# PSU_MAX1831_3V3_ALT.net
KiCad netlist of a schematic drawn in Altium Designer
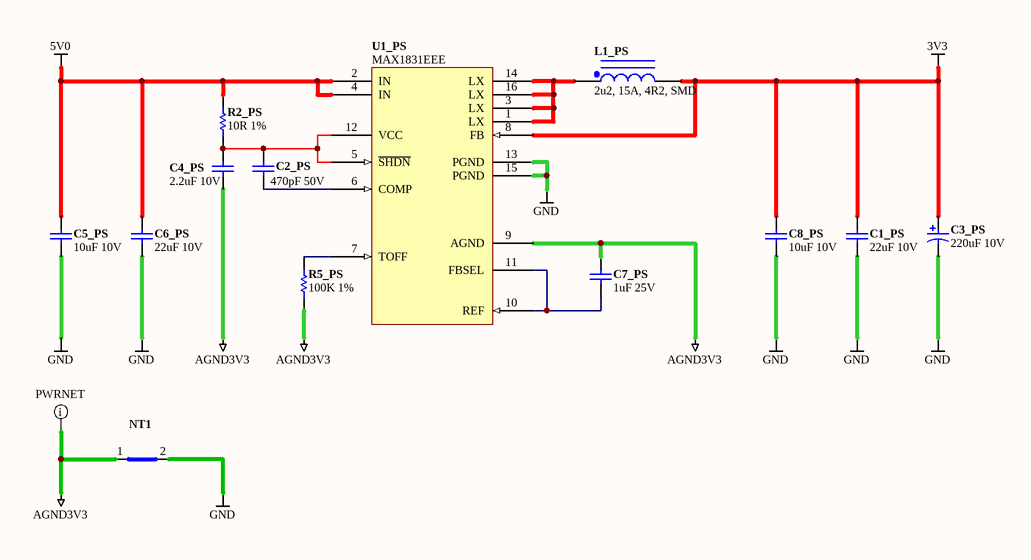
[diagram p0: PSU_MAX1831_3V3_ALT.SchDoc]

(export (version "E")
  (design (tool "Eeschema 10.0.6"))
  (components
    (comp (ref "C1_PS")
      (value "22uF 10V")
      (footprint "CAPC3225-STAR")
      (description "Capacitor, Ceramic, 22uF -20%/+80% 10V 1210 (3225) Y5V")
      (fields (field (name "TOLERANCE") "-20 / +80 %"))
      (libsource (lib "AltiumDesignLibrary") (part "CAP-NP"))
    )
    (comp (ref "C2_PS")
      (value "470pF 50V")
      (footprint "CAPC1005-STAR")
      (description "Capacitor, Ceramic, 470pF 5% 50V 0402 (1005) COG")
      (fields (field (name "TOLERANCE") "5 %"))
      (libsource (lib "AltiumDesignLibrary") (part "CAP-NP"))
    )
    (comp (ref "C3_PS")
      (value "220uF 10V")
      (footprint "CAPC7343-STAR")
      (description "Capacitor, Tantalum, 220uF 10% 10V MCCT-D (7343-31)")
      (fields (field (name "TOLERANCE") "10 %"))
      (libsource (lib "AltiumDesignLibrary") (part "CAP-P"))
    )
    (comp (ref "C4_PS")
      (value "2.2uF 10V")
      (footprint "CAPC1608-STAR")
      (description "Capacitor, Ceramic, 2.2uF 10% 10V 0603 (1608) X5R")
      (fields (field (name "TOLERANCE") "10 %"))
      (libsource (lib "AltiumDesignLibrary") (part "CAP-NP"))
    )
    (comp (ref "C5_PS")
      (value "10uF 10V")
      (footprint "CAPC2012-STAR")
      (description "Capacitor, Ceramic, 10uF 10% 10V 0805 (2012) X5R")
      (fields (field (name "TOLERANCE") "10 %"))
      (libsource (lib "AltiumDesignLibrary") (part "CAP-NP"))
    )
    (comp (ref "C6_PS")
      (value "22uF 10V")
      (footprint "CAPC3225-STAR")
      (description "Capacitor, Ceramic, 22uF -20%/+80% 10V 1210 (3225) Y5V")
      (fields (field (name "TOLERANCE") "-20 / +80 %"))
      (libsource (lib "AltiumDesignLibrary") (part "CAP-NP"))
    )
    (comp (ref "C7_PS")
      (value "1uF 25V")
      (footprint "CAPC3216-STAR")
      (description "Capacitor, Ceramic, 1uF 10% 25V 1206 (3216) X7R")
      (fields (field (name "TOLERANCE") "10 %"))
      (libsource (lib "AltiumDesignLibrary") (part "CAP-NP"))
    )
    (comp (ref "C8_PS")
      (value "10uF 10V")
      (footprint "CAPC2012-STAR")
      (description "Capacitor, Ceramic, 10uF 10% 10V 0805 (2012) X5R")
      (fields (field (name "TOLERANCE") "10 %"))
      (libsource (lib "AltiumDesignLibrary") (part "CAP-NP"))
    )
    (comp (ref "L1_PS")
      (value "2u2, 15A, 4R2, SMD")
      (footprint "IND-EPCOS-SMD-B82559")
      (description "Inductor, 2.2uH, 15A, 4R2, SMD")
      (libsource (lib "AltiumDesignLibrary") (part "IND-IRON-DOT"))
    )
    (comp (ref "NT1")
      (value "Net Tie SMT2")
      (footprint "NETTIE-SMT2-31X51")
      (description "Net-Tie, Surface Mount, 2 x 1.6mm x 0.8mm SMT Pads - For 0.8mm Track")
      (libsource (lib "AltiumDesignLibrary") (part "NETTIE-SMT2"))
    )
    (comp (ref "R2_PS")
      (value "10R 1%")
      (footprint "RESC1005-STAR")
      (description "Resistor, 10R 1% 0402 (1005)")
      (fields (field (name "TOLERANCE") "1 %"))
      (libsource (lib "AltiumDesignLibrary") (part "RES"))
    )
    (comp (ref "R5_PS")
      (value "100K 1%")
      (footprint "RESC1005-STAR")
      (description "Resistor, 100K 1% 0402 (1005)")
      (fields (field (name "TOLERANCE") "1 %"))
      (libsource (lib "AltiumDesignLibrary") (part "RES"))
    )
    (comp (ref "U1_PS")
      (value "MAX1831EEE")
      (footprint "SOP63P602-16")
      (libsource (lib "AltiumDesignLibrary") (part "MAX1831-ALT"))
    )
  )
  (nets
    (net (code "1") (name "3V3") (class "Default")
      (node (ref "C1_PS") (pin "1") (pinfunction "1_1") (pintype "passive"))
      (node (ref "C3_PS") (pin "1") (pinfunction "1_1") (pintype "passive"))
      (node (ref "C8_PS") (pin "1") (pinfunction "1_1") (pintype "passive"))
      (node (ref "L1_PS") (pin "2") (pinfunction "2_2") (pintype "passive"))
      (node (ref "U1_PS") (pin "8") (pinfunction "FB_8") (pintype "input"))
    )
    (net (code "2") (name "5V0") (class "Default")
      (node (ref "C5_PS") (pin "1") (pinfunction "1_1") (pintype "passive"))
      (node (ref "C6_PS") (pin "1") (pinfunction "1_1") (pintype "passive"))
      (node (ref "R2_PS") (pin "1") (pinfunction "1_1") (pintype "passive"))
      (node (ref "U1_PS") (pin "2") (pinfunction "IN_2") (pintype "power_in"))
      (node (ref "U1_PS") (pin "4") (pinfunction "IN_4") (pintype "power_in"))
    )
    (net (code "3") (name "AGND3V3") (class "Default")
      (node (ref "C4_PS") (pin "2") (pinfunction "2_2") (pintype "passive"))
      (node (ref "C7_PS") (pin "1") (pinfunction "1_1") (pintype "passive"))
      (node (ref "NT1") (pin "1") (pinfunction "Net1_1") (pintype "passive"))
      (node (ref "R5_PS") (pin "2") (pinfunction "2_2") (pintype "passive"))
      (node (ref "U1_PS") (pin "9") (pinfunction "AGND_9") (pintype "power_in"))
    )
    (net (code "4") (name "GND") (class "Default")
      (node (ref "C1_PS") (pin "2") (pinfunction "2_2") (pintype "passive"))
      (node (ref "C3_PS") (pin "2") (pinfunction "2_2") (pintype "passive"))
      (node (ref "C5_PS") (pin "2") (pinfunction "2_2") (pintype "passive"))
      (node (ref "C6_PS") (pin "2") (pinfunction "2_2") (pintype "passive"))
      (node (ref "C8_PS") (pin "2") (pinfunction "2_2") (pintype "passive"))
      (node (ref "NT1") (pin "2") (pinfunction "Net2_2") (pintype "passive"))
      (node (ref "U1_PS") (pin "13") (pinfunction "PGND_13") (pintype "power_in"))
      (node (ref "U1_PS") (pin "15") (pinfunction "PGND_15") (pintype "power_in"))
    )
    (net (code "5") (name "Net-(L1_PS-Pad1)") (class "Default")
      (node (ref "L1_PS") (pin "1") (pinfunction "1_1") (pintype "passive"))
      (node (ref "U1_PS") (pin "1") (pinfunction "LX_1") (pintype "power_in"))
      (node (ref "U1_PS") (pin "14") (pinfunction "LX_14") (pintype "power_in"))
      (node (ref "U1_PS") (pin "16") (pinfunction "LX_16") (pintype "power_in"))
      (node (ref "U1_PS") (pin "3") (pinfunction "LX_3") (pintype "power_in"))
    )
    (net (code "6") (name "Net-(U1_PS-COMP)") (class "Default")
      (node (ref "C2_PS") (pin "2") (pinfunction "2_2") (pintype "passive"))
      (node (ref "U1_PS") (pin "6") (pinfunction "COMP_6") (pintype "input"))
    )
    (net (code "7") (name "Net-(U1_PS-FBSEL)") (class "Default")
      (node (ref "C7_PS") (pin "2") (pinfunction "2_2") (pintype "passive"))
      (node (ref "U1_PS") (pin "10") (pinfunction "REF_10") (pintype "input"))
      (node (ref "U1_PS") (pin "11") (pinfunction "FBSEL_11") (pintype "passive"))
    )
    (net (code "8") (name "Net-(U1_PS-TOFF)") (class "Default")
      (node (ref "R5_PS") (pin "1") (pinfunction "1_1") (pintype "passive"))
      (node (ref "U1_PS") (pin "7") (pinfunction "TOFF_7") (pintype "input"))
    )
    (net (code "9") (name "Net-(U1_PS-VCC)") (class "Default")
      (node (ref "C2_PS") (pin "1") (pinfunction "1_1") (pintype "passive"))
      (node (ref "C4_PS") (pin "1") (pinfunction "1_1") (pintype "passive"))
      (node (ref "R2_PS") (pin "2") (pinfunction "2_2") (pintype "passive"))
      (node (ref "U1_PS") (pin "12") (pinfunction "VCC_12") (pintype "power_in"))
      (node (ref "U1_PS") (pin "5") (pinfunction "~{SHDN}_5") (pintype "input"))
    )
  )
)
